# Enclosure_Front_NusbioPlus.net
KiCad netlist of a schematic drawn in EAGLE
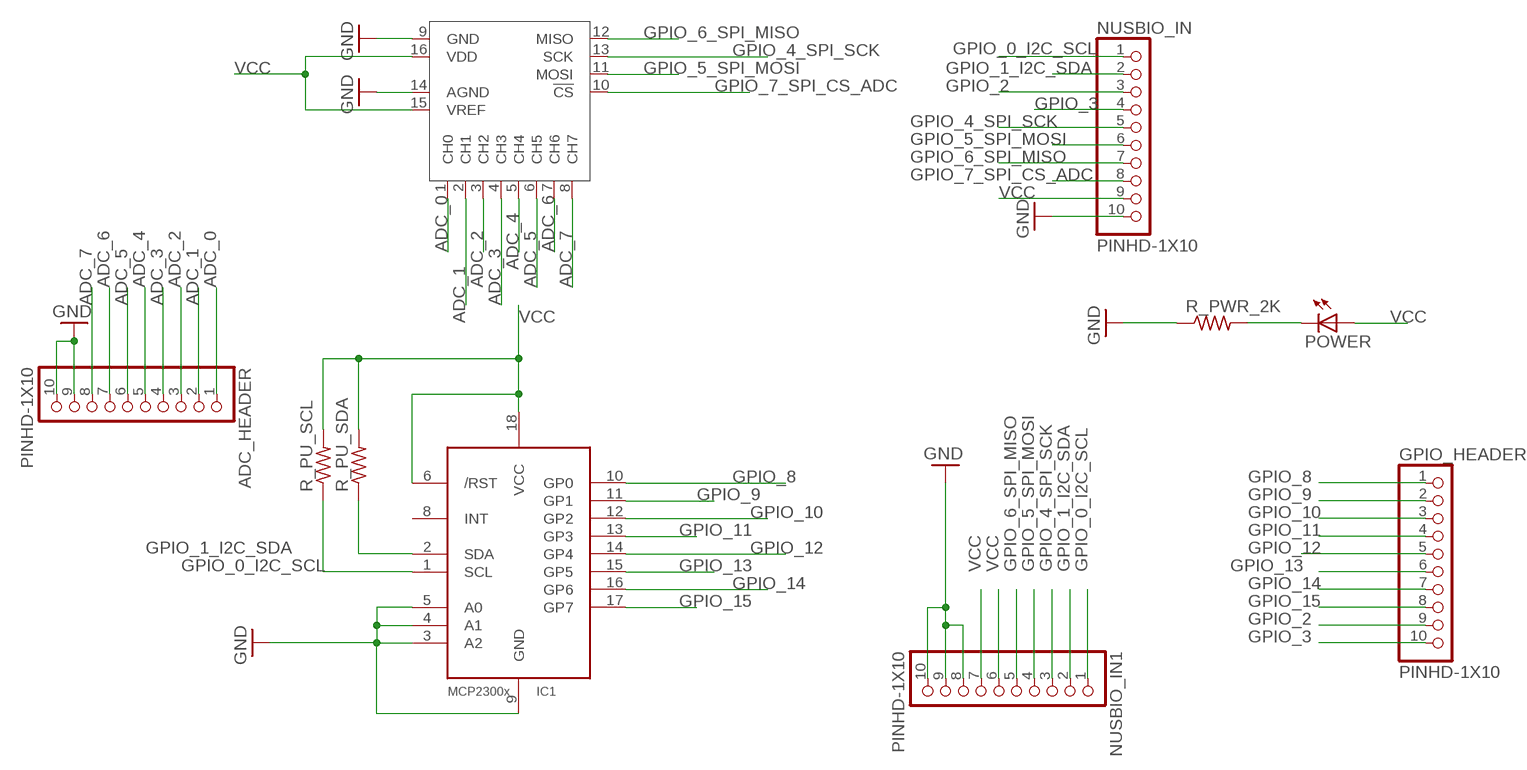
[diagram p0: schematic, sheet 1]

(export (version "E")
  (design (tool "Eeschema 10.0.6"))
  (components
    (comp (ref "ADC_HEADER")
      (value "PINHD-1X10")
      (footprint "eagle-import:1X10-BIG")
      (libsource (lib "eagle-import") (part "PINHD-1X10"))
    )
    (comp (ref "GPIO_HEADER")
      (value "PINHD-1X10")
      (footprint "eagle-import:1X10-BIG")
      (libsource (lib "eagle-import") (part "PINHD-1X10"))
    )
    (comp (ref "IC1")
      (value "MCP23008/SO")
      (footprint "eagle-import:SO18W")
      (libsource (lib "eagle-import") (part "MCP23008/SO"))
    )
    (comp (ref "NUSBIO_IN")
      (value "PINHD-1X10")
      (footprint "eagle-import:1X10-BIG")
      (libsource (lib "eagle-import") (part "PINHD-1X10"))
    )
    (comp (ref "NUSBIO_IN1")
      (value "PINHD-1X10")
      (footprint "eagle-import:1X10-BIG")
      (libsource (lib "eagle-import") (part "PINHD-1X10"))
    )
    (comp (ref "POWER")
      (value "LEDSMT1206")
      (footprint "eagle-import:1206")
      (libsource (lib "eagle-import") (part "LEDSMT1206"))
    )
    (comp (ref "R_PU_SCL")
      (value "R-US_R1206")
      (footprint "eagle-import:R1206")
      (libsource (lib "eagle-import") (part "R-US_R1206"))
    )
    (comp (ref "R_PU_SDA")
      (value "R-US_R1206")
      (footprint "eagle-import:R1206")
      (libsource (lib "eagle-import") (part "R-US_R1206"))
    )
    (comp (ref "R_PWR_2K")
      (value "R-US_R1206")
      (footprint "eagle-import:R1206")
      (libsource (lib "eagle-import") (part "R-US_R1206"))
    )
    (comp (ref "U$1")
      (value "MCP3008SL")
      (footprint "eagle-import:SO16")
      (libsource (lib "eagle-import") (part "MCP3008SL"))
    )
  )
  (nets
    (net (code "1") (name "/ADC_0") (class "Default")
      (node (ref "ADC_HEADER") (pin "1") (pinfunction "1_1") (pintype "passive"))
      (node (ref "U$1") (pin "1") (pinfunction "CH0_1") (pintype "input"))
    )
    (net (code "2") (name "/ADC_1") (class "Default")
      (node (ref "ADC_HEADER") (pin "2") (pinfunction "2_2") (pintype "passive"))
      (node (ref "U$1") (pin "2") (pinfunction "CH1_2") (pintype "input"))
    )
    (net (code "3") (name "/ADC_2") (class "Default")
      (node (ref "ADC_HEADER") (pin "3") (pinfunction "3_3") (pintype "passive"))
      (node (ref "U$1") (pin "3") (pinfunction "CH2_3") (pintype "input"))
    )
    (net (code "4") (name "/ADC_3") (class "Default")
      (node (ref "ADC_HEADER") (pin "4") (pinfunction "4_4") (pintype "passive"))
      (node (ref "U$1") (pin "4") (pinfunction "CH3_4") (pintype "input"))
    )
    (net (code "5") (name "/ADC_4") (class "Default")
      (node (ref "ADC_HEADER") (pin "5") (pinfunction "5_5") (pintype "passive"))
      (node (ref "U$1") (pin "5") (pinfunction "CH4_5") (pintype "input"))
    )
    (net (code "6") (name "/ADC_5") (class "Default")
      (node (ref "ADC_HEADER") (pin "6") (pinfunction "6_6") (pintype "passive"))
      (node (ref "U$1") (pin "6") (pinfunction "CH5_6") (pintype "input"))
    )
    (net (code "7") (name "/ADC_6") (class "Default")
      (node (ref "ADC_HEADER") (pin "7") (pinfunction "7_7") (pintype "passive"))
      (node (ref "U$1") (pin "7") (pinfunction "CH6_7") (pintype "input"))
    )
    (net (code "8") (name "/ADC_7") (class "Default")
      (node (ref "ADC_HEADER") (pin "8") (pinfunction "8_8") (pintype "passive"))
      (node (ref "U$1") (pin "8") (pinfunction "CH7_8") (pintype "input"))
    )
    (net (code "9") (name "/GPIO_0_I2C_SCL") (class "Default")
      (node (ref "IC1") (pin "1") (pinfunction "SCL_1") (pintype "bidirectional"))
      (node (ref "NUSBIO_IN") (pin "1") (pinfunction "1_1") (pintype "passive"))
      (node (ref "NUSBIO_IN1") (pin "1") (pinfunction "1_1") (pintype "passive"))
      (node (ref "R_PU_SCL") (pin "1") (pinfunction "1_1") (pintype "passive"))
    )
    (net (code "10") (name "/GPIO_1_I2C_SDA") (class "Default")
      (node (ref "IC1") (pin "2") (pinfunction "SDA_2") (pintype "bidirectional"))
      (node (ref "NUSBIO_IN") (pin "2") (pinfunction "2_2") (pintype "passive"))
      (node (ref "NUSBIO_IN1") (pin "2") (pinfunction "2_2") (pintype "passive"))
      (node (ref "R_PU_SDA") (pin "1") (pinfunction "1_1") (pintype "passive"))
    )
    (net (code "11") (name "/GPIO_2") (class "Default")
      (node (ref "GPIO_HEADER") (pin "9") (pinfunction "9_9") (pintype "passive"))
      (node (ref "NUSBIO_IN") (pin "3") (pinfunction "3_3") (pintype "passive"))
    )
    (net (code "12") (name "/GPIO_3") (class "Default")
      (node (ref "GPIO_HEADER") (pin "10") (pinfunction "10_10") (pintype "passive"))
      (node (ref "NUSBIO_IN") (pin "4") (pinfunction "4_4") (pintype "passive"))
    )
    (net (code "13") (name "/GPIO_4_SPI_SCK") (class "Default")
      (node (ref "NUSBIO_IN") (pin "5") (pinfunction "5_5") (pintype "passive"))
      (node (ref "NUSBIO_IN1") (pin "3") (pinfunction "3_3") (pintype "passive"))
      (node (ref "U$1") (pin "13") (pinfunction "SCK_13") (pintype "input"))
    )
    (net (code "14") (name "/GPIO_5_SPI_MOSI") (class "Default")
      (node (ref "NUSBIO_IN") (pin "6") (pinfunction "6_6") (pintype "passive"))
      (node (ref "NUSBIO_IN1") (pin "4") (pinfunction "4_4") (pintype "passive"))
      (node (ref "U$1") (pin "11") (pinfunction "MOSI_11") (pintype "input"))
    )
    (net (code "15") (name "/GPIO_6_SPI_MISO") (class "Default")
      (node (ref "NUSBIO_IN") (pin "7") (pinfunction "7_7") (pintype "passive"))
      (node (ref "NUSBIO_IN1") (pin "5") (pinfunction "5_5") (pintype "passive"))
      (node (ref "U$1") (pin "12") (pinfunction "MISO_12") (pintype "output"))
    )
    (net (code "16") (name "/GPIO_7_SPI_CS_ADC") (class "Default")
      (node (ref "NUSBIO_IN") (pin "8") (pinfunction "8_8") (pintype "passive"))
      (node (ref "U$1") (pin "10") (pinfunction "~{CS}_10") (pintype "input"))
    )
    (net (code "17") (name "/GPIO_8") (class "Default")
      (node (ref "GPIO_HEADER") (pin "1") (pinfunction "1_1") (pintype "passive"))
      (node (ref "IC1") (pin "10") (pinfunction "GP0_10") (pintype "bidirectional"))
    )
    (net (code "18") (name "/GPIO_9") (class "Default")
      (node (ref "GPIO_HEADER") (pin "2") (pinfunction "2_2") (pintype "passive"))
      (node (ref "IC1") (pin "11") (pinfunction "GP1_11") (pintype "bidirectional"))
    )
    (net (code "19") (name "/GPIO_10") (class "Default")
      (node (ref "GPIO_HEADER") (pin "3") (pinfunction "3_3") (pintype "passive"))
      (node (ref "IC1") (pin "12") (pinfunction "GP2_12") (pintype "bidirectional"))
    )
    (net (code "20") (name "/GPIO_11") (class "Default")
      (node (ref "GPIO_HEADER") (pin "4") (pinfunction "4_4") (pintype "passive"))
      (node (ref "IC1") (pin "13") (pinfunction "GP3_13") (pintype "bidirectional"))
    )
    (net (code "21") (name "/GPIO_12") (class "Default")
      (node (ref "GPIO_HEADER") (pin "5") (pinfunction "5_5") (pintype "passive"))
      (node (ref "IC1") (pin "14") (pinfunction "GP4_14") (pintype "bidirectional"))
    )
    (net (code "22") (name "/GPIO_13") (class "Default")
      (node (ref "GPIO_HEADER") (pin "6") (pinfunction "6_6") (pintype "passive"))
      (node (ref "IC1") (pin "15") (pinfunction "GP5_15") (pintype "bidirectional"))
    )
    (net (code "23") (name "/GPIO_14") (class "Default")
      (node (ref "GPIO_HEADER") (pin "7") (pinfunction "7_7") (pintype "passive"))
      (node (ref "IC1") (pin "16") (pinfunction "GP6_16") (pintype "bidirectional"))
    )
    (net (code "24") (name "/GPIO_15") (class "Default")
      (node (ref "GPIO_HEADER") (pin "8") (pinfunction "8_8") (pintype "passive"))
      (node (ref "IC1") (pin "17") (pinfunction "GP7_17") (pintype "bidirectional"))
    )
    (net (code "25") (name "/VCC") (class "Default")
      (node (ref "IC1") (pin "18") (pinfunction "VCC_18") (pintype "power_in"))
      (node (ref "IC1") (pin "6") (pinfunction "/RST_6") (pintype "input"))
      (node (ref "NUSBIO_IN") (pin "9") (pinfunction "9_9") (pintype "passive"))
      (node (ref "NUSBIO_IN1") (pin "6") (pinfunction "6_6") (pintype "passive"))
      (node (ref "NUSBIO_IN1") (pin "7") (pinfunction "7_7") (pintype "passive"))
      (node (ref "POWER") (pin "A") (pinfunction "A_A") (pintype "passive"))
      (node (ref "R_PU_SCL") (pin "2") (pinfunction "2_2") (pintype "passive"))
      (node (ref "R_PU_SDA") (pin "2") (pinfunction "2_2") (pintype "passive"))
      (node (ref "U$1") (pin "15") (pinfunction "VREF_15") (pintype "power_in"))
      (node (ref "U$1") (pin "16") (pinfunction "VDD_16") (pintype "power_in"))
    )
    (net (code "26") (name "GND") (class "Default")
      (node (ref "ADC_HEADER") (pin "10") (pinfunction "10_10") (pintype "passive"))
      (node (ref "ADC_HEADER") (pin "9") (pinfunction "9_9") (pintype "passive"))
      (node (ref "IC1") (pin "3") (pinfunction "A2_3") (pintype "input"))
      (node (ref "IC1") (pin "4") (pinfunction "A1_4") (pintype "input"))
      (node (ref "IC1") (pin "5") (pinfunction "A0_5") (pintype "input"))
      (node (ref "IC1") (pin "9") (pinfunction "GND_9") (pintype "power_in"))
      (node (ref "NUSBIO_IN") (pin "10") (pinfunction "10_10") (pintype "passive"))
      (node (ref "NUSBIO_IN1") (pin "10") (pinfunction "10_10") (pintype "passive"))
      (node (ref "NUSBIO_IN1") (pin "8") (pinfunction "8_8") (pintype "passive"))
      (node (ref "NUSBIO_IN1") (pin "9") (pinfunction "9_9") (pintype "passive"))
      (node (ref "R_PWR_2K") (pin "1") (pinfunction "1_1") (pintype "passive"))
      (node (ref "U$1") (pin "14") (pinfunction "AGND_14") (pintype "power_in"))
      (node (ref "U$1") (pin "9") (pinfunction "GND_9") (pintype "power_in"))
    )
    (net (code "27") (name "Net-(POWER-PadC)") (class "Default")
      (node (ref "POWER") (pin "C") (pinfunction "C_C") (pintype "passive"))
      (node (ref "R_PWR_2K") (pin "2") (pinfunction "2_2") (pintype "passive"))
    )
    (net (code "28") (name "unconnected-(IC1-INT-Pad8)") (class "Default")
      (node (ref "IC1") (pin "8") (pinfunction "INT_8") (pintype "output"))
    )
  )
)
